# 07_FPGA_banks_1_2_3_4.net
KiCad netlist of a schematic drawn in Altium Designer
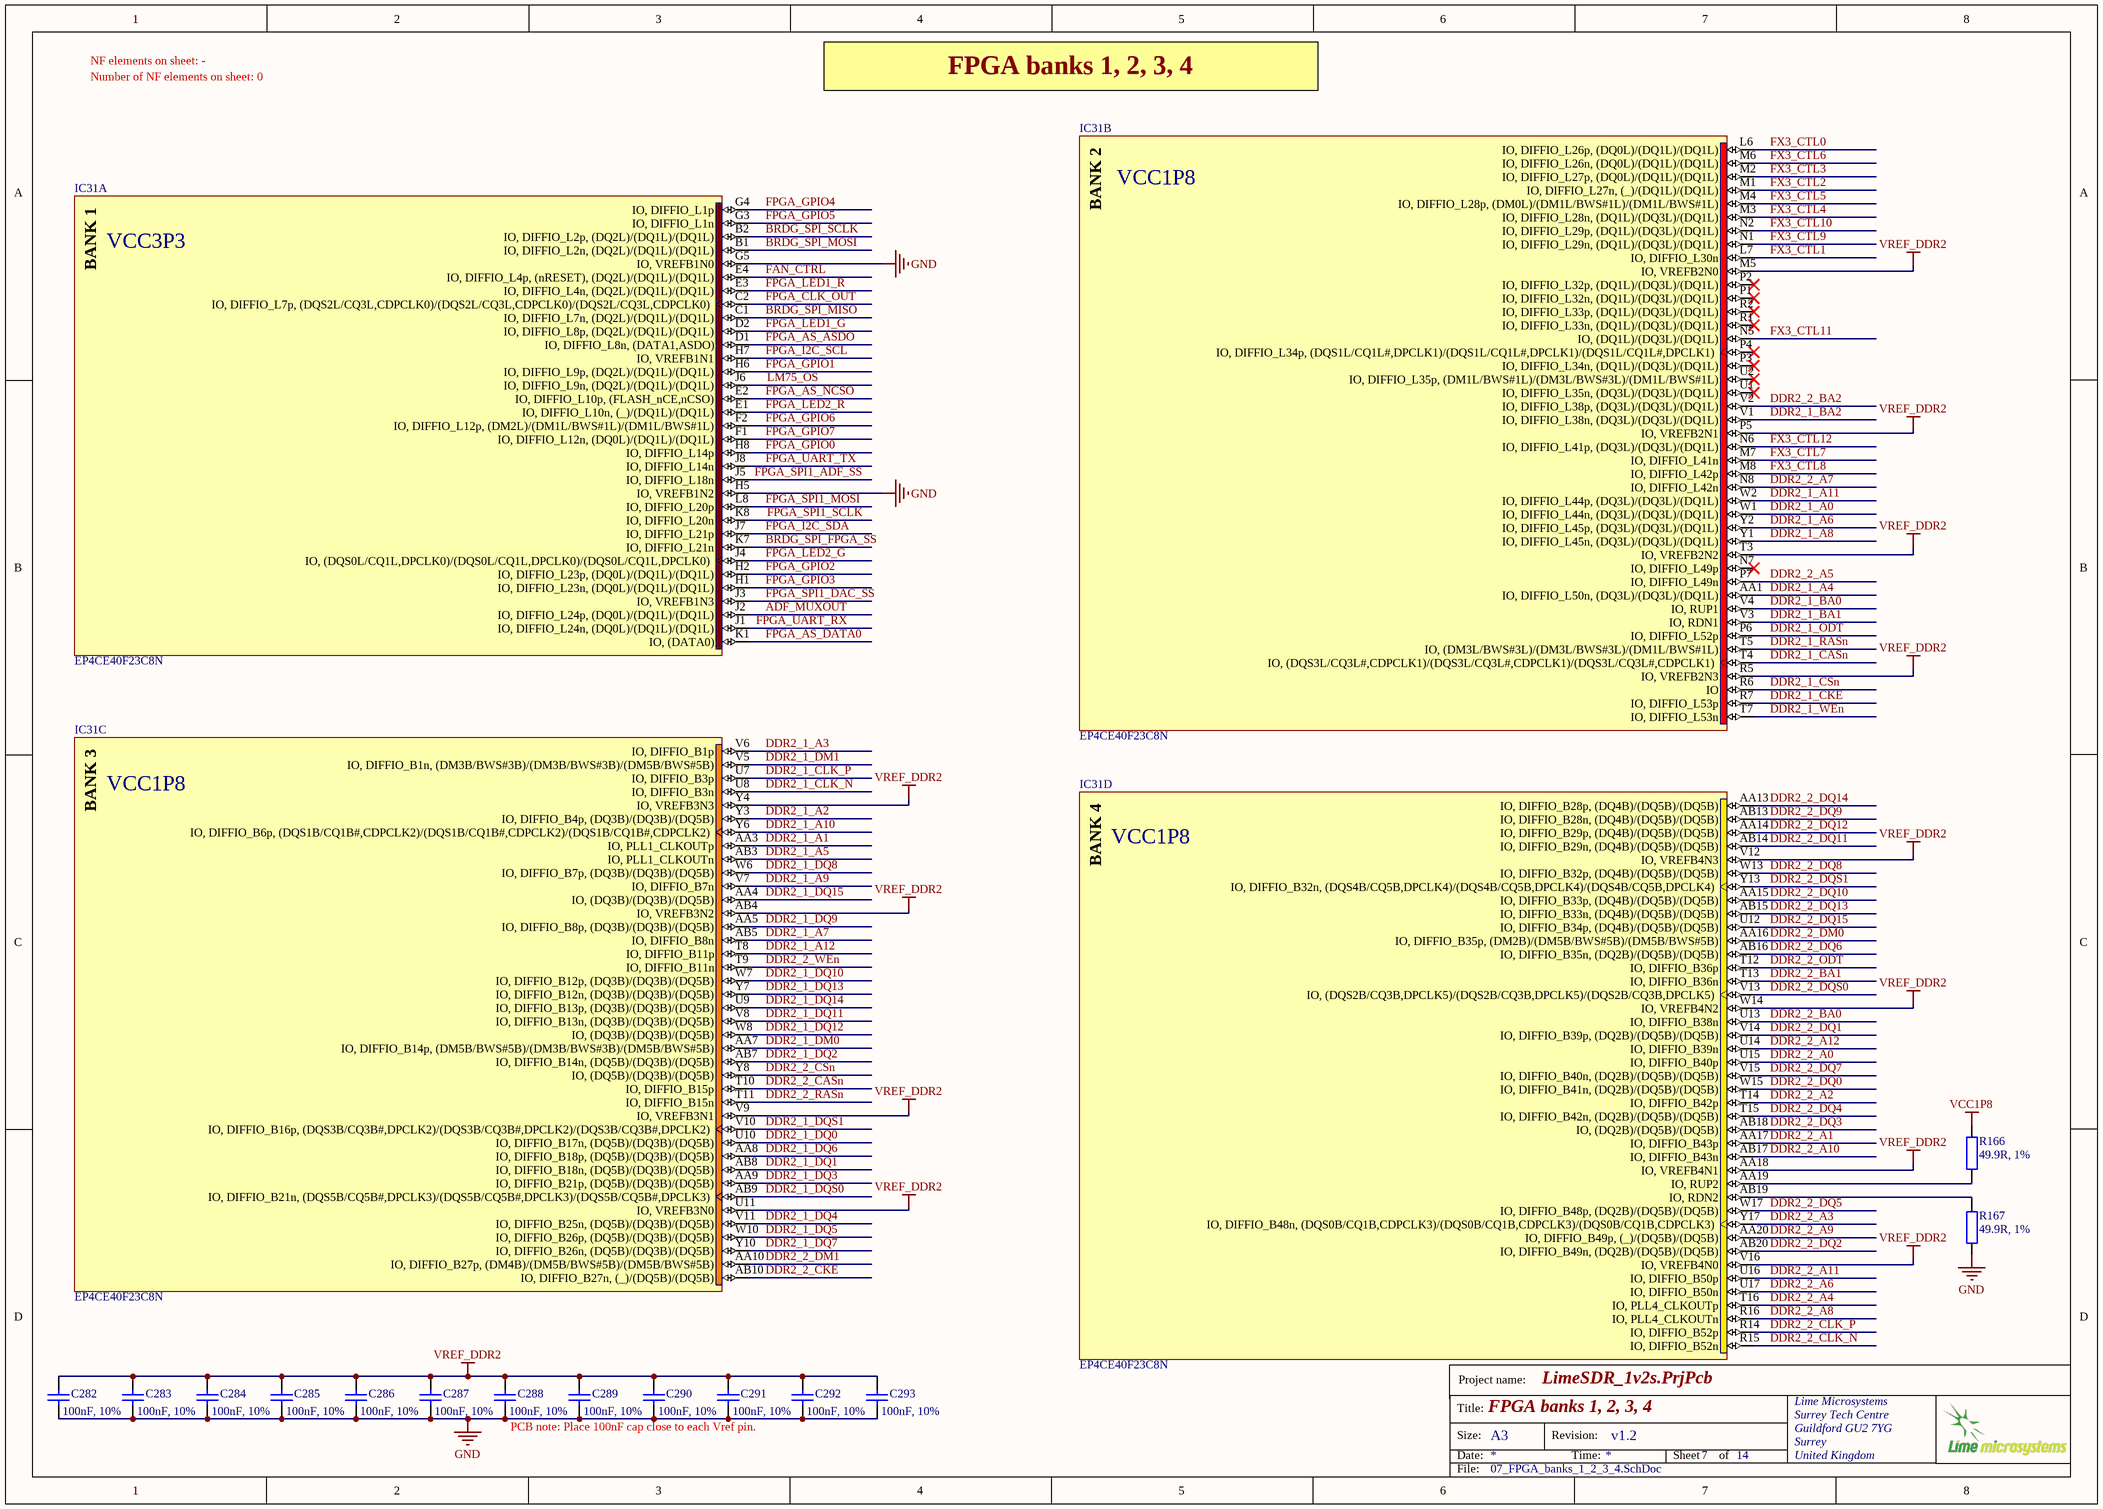
[diagram p0: 07_FPGA_banks_1_2_3_4.SchDoc]

(export (version "E")
  (design (tool "Eeschema 10.0.6"))
  (components
    (comp (ref "C282")
      (value "100nF, 10%")
      (footprint "CAP0402")
      (fields
        (field (name "TOLERANCE") "10 %")
        (field (name "MANUFACTURER") "Murata Electronics")
        (field (name "MANUFACTURER PART NUMBER") "GRM155R71C104KA88D")
      )
      (libsource (lib "LimeFPGAboard_schLib") (part "Cap_0603"))
    )
    (comp (ref "C283")
      (value "100nF, 10%")
      (footprint "CAP0402")
      (fields
        (field (name "TOLERANCE") "10 %")
        (field (name "MANUFACTURER") "Murata Electronics")
        (field (name "MANUFACTURER PART NUMBER") "GRM155R71C104KA88D")
      )
      (libsource (lib "LimeFPGAboard_schLib") (part "Cap_0603"))
    )
    (comp (ref "C284")
      (value "100nF, 10%")
      (footprint "CAP0402")
      (fields
        (field (name "TOLERANCE") "10 %")
        (field (name "MANUFACTURER") "Murata Electronics")
        (field (name "MANUFACTURER PART NUMBER") "GRM155R71C104KA88D")
      )
      (libsource (lib "LimeFPGAboard_schLib") (part "Cap_0603"))
    )
    (comp (ref "C285")
      (value "100nF, 10%")
      (footprint "CAP0402")
      (fields
        (field (name "TOLERANCE") "10 %")
        (field (name "MANUFACTURER") "Murata Electronics")
        (field (name "MANUFACTURER PART NUMBER") "GRM155R71C104KA88D")
      )
      (libsource (lib "LimeFPGAboard_schLib") (part "Cap_0603"))
    )
    (comp (ref "C286")
      (value "100nF, 10%")
      (footprint "CAP0402")
      (fields
        (field (name "TOLERANCE") "10 %")
        (field (name "MANUFACTURER") "Murata Electronics")
        (field (name "MANUFACTURER PART NUMBER") "GRM155R71C104KA88D")
      )
      (libsource (lib "LimeFPGAboard_schLib") (part "Cap_0603"))
    )
    (comp (ref "C287")
      (value "100nF, 10%")
      (footprint "CAP0402")
      (fields
        (field (name "TOLERANCE") "10 %")
        (field (name "MANUFACTURER") "Murata Electronics")
        (field (name "MANUFACTURER PART NUMBER") "GRM155R71C104KA88D")
      )
      (libsource (lib "LimeFPGAboard_schLib") (part "Cap_0603"))
    )
    (comp (ref "C288")
      (value "100nF, 10%")
      (footprint "CAP0402")
      (fields
        (field (name "TOLERANCE") "10 %")
        (field (name "MANUFACTURER") "Murata Electronics")
        (field (name "MANUFACTURER PART NUMBER") "GRM155R71C104KA88D")
      )
      (libsource (lib "LimeFPGAboard_schLib") (part "Cap_0603"))
    )
    (comp (ref "C289")
      (value "100nF, 10%")
      (footprint "CAP0402")
      (fields
        (field (name "TOLERANCE") "10 %")
        (field (name "MANUFACTURER") "Murata Electronics")
        (field (name "MANUFACTURER PART NUMBER") "GRM155R71C104KA88D")
      )
      (libsource (lib "LimeFPGAboard_schLib") (part "Cap_0603"))
    )
    (comp (ref "C290")
      (value "100nF, 10%")
      (footprint "CAP0402")
      (fields
        (field (name "TOLERANCE") "10 %")
        (field (name "MANUFACTURER") "Murata Electronics")
        (field (name "MANUFACTURER PART NUMBER") "GRM155R71C104KA88D")
      )
      (libsource (lib "LimeFPGAboard_schLib") (part "Cap_0603"))
    )
    (comp (ref "C291")
      (value "100nF, 10%")
      (footprint "CAP0402")
      (fields
        (field (name "TOLERANCE") "10 %")
        (field (name "MANUFACTURER") "Murata Electronics")
        (field (name "MANUFACTURER PART NUMBER") "GRM155R71C104KA88D")
      )
      (libsource (lib "LimeFPGAboard_schLib") (part "Cap_0603"))
    )
    (comp (ref "C292")
      (value "100nF, 10%")
      (footprint "CAP0402")
      (fields
        (field (name "TOLERANCE") "10 %")
        (field (name "MANUFACTURER") "Murata Electronics")
        (field (name "MANUFACTURER PART NUMBER") "GRM155R71C104KA88D")
      )
      (libsource (lib "LimeFPGAboard_schLib") (part "Cap_0603"))
    )
    (comp (ref "C293")
      (value "100nF, 10%")
      (footprint "CAP0402")
      (fields
        (field (name "TOLERANCE") "10 %")
        (field (name "MANUFACTURER") "Murata Electronics")
        (field (name "MANUFACTURER PART NUMBER") "GRM155R71C104KA88D")
      )
      (libsource (lib "LimeFPGAboard_schLib") (part "Cap_0603"))
    )
    (comp (ref "IC31")
      (value "EP4CE40F23C8N")
      (footprint "FBGA484_A-240")
      (description "IC FPGA 328 I/O 484FBGA")
      (fields (field (name "MANUFACTURER") "Altera"))
      (libsource (lib "LimeMicroAltiumLib_schLib") (part "EP4CE40F23C7N"))
    )
    (comp (ref "R166")
      (value "49.9R, 1%")
      (footprint "LimeMicroAltiumLib_pcbLib:RES0402")
      (fields
        (field (name "TOLERANCE") "±1%")
        (field (name "MANUFACTURER") "Samsung Electro-Mechanics America, Inc.")
        (field (name "MANUFACTURER PART NUMBER") "RC1005F49R9CS")
      )
      (libsource (lib "LimeMicroAltiumLib_schLib") (part "Res_0402"))
    )
    (comp (ref "R167")
      (value "49.9R, 1%")
      (footprint "LimeMicroAltiumLib_pcbLib:RES0402")
      (fields
        (field (name "TOLERANCE") "±1%")
        (field (name "MANUFACTURER") "Samsung Electro-Mechanics America, Inc.")
        (field (name "MANUFACTURER PART NUMBER") "RC1005F49R9CS")
      )
      (libsource (lib "LimeMicroAltiumLib_schLib") (part "Res_0402"))
    )
  )
  (nets
    (net (code "1") (name "/ADF_MUXOUT") (class "Default")
      (node (ref "IC31") (pin "J2") (pinfunction "IO,_DIFFIO_L24p,_(DQ0L)/(DQ1L)/(DQ1L)_J2") (pintype "bidirectional"))
    )
    (net (code "2") (name "/BRDG_SPI_FPGA_SS") (class "Default")
      (node (ref "IC31") (pin "K7") (pinfunction "IO,_DIFFIO_L21n_K7") (pintype "bidirectional"))
    )
    (net (code "3") (name "/BRDG_SPI_MISO") (class "Default")
      (node (ref "IC31") (pin "C1") (pinfunction "IO,_DIFFIO_L7n,_(DQ2L)/(DQ1L)/(DQ1L)_C1") (pintype "bidirectional"))
    )
    (net (code "4") (name "/BRDG_SPI_MOSI") (class "Default")
      (node (ref "IC31") (pin "B1") (pinfunction "IO,_DIFFIO_L2n,_(DQ2L)/(DQ1L)/(DQ1L)_B1") (pintype "bidirectional"))
    )
    (net (code "5") (name "/BRDG_SPI_SCLK") (class "Default")
      (node (ref "IC31") (pin "B2") (pinfunction "IO,_DIFFIO_L2p,_(DQ2L)/(DQ1L)/(DQ1L)_B2") (pintype "bidirectional"))
    )
    (net (code "6") (name "/DDR2_1_A0") (class "Default")
      (node (ref "IC31") (pin "W1") (pinfunction "IO,_DIFFIO_L44n,_(DQ3L)/(DQ3L)/(DQ1L)_W1") (pintype "bidirectional"))
    )
    (net (code "7") (name "/DDR2_1_A1") (class "Default")
      (node (ref "IC31") (pin "AA3") (pinfunction "IO,_PLL1_CLKOUTp_AA3") (pintype "bidirectional"))
    )
    (net (code "8") (name "/DDR2_1_A2") (class "Default")
      (node (ref "IC31") (pin "Y3") (pinfunction "IO,_DIFFIO_B4p,_(DQ3B)/(DQ3B)/(DQ5B)_Y3") (pintype "bidirectional"))
    )
    (net (code "9") (name "/DDR2_1_A3") (class "Default")
      (node (ref "IC31") (pin "V6") (pinfunction "IO,_DIFFIO_B1p_V6") (pintype "bidirectional"))
    )
    (net (code "10") (name "/DDR2_1_A4") (class "Default")
      (node (ref "IC31") (pin "AA1") (pinfunction "IO,_DIFFIO_L50n,_(DQ3L)/(DQ3L)/(DQ1L)_AA1") (pintype "bidirectional"))
    )
    (net (code "11") (name "/DDR2_1_A5") (class "Default")
      (node (ref "IC31") (pin "AB3") (pinfunction "IO,_PLL1_CLKOUTn_AB3") (pintype "bidirectional"))
    )
    (net (code "12") (name "/DDR2_1_A6") (class "Default")
      (node (ref "IC31") (pin "Y2") (pinfunction "IO,_DIFFIO_L45p,_(DQ3L)/(DQ3L)/(DQ1L)_Y2") (pintype "bidirectional"))
    )
    (net (code "13") (name "/DDR2_1_A7") (class "Default")
      (node (ref "IC31") (pin "AB5") (pinfunction "IO,_DIFFIO_B8n_AB5") (pintype "bidirectional"))
    )
    (net (code "14") (name "/DDR2_1_A8") (class "Default")
      (node (ref "IC31") (pin "Y1") (pinfunction "IO,_DIFFIO_L45n,_(DQ3L)/(DQ3L)/(DQ1L)_Y1") (pintype "bidirectional"))
    )
    (net (code "15") (name "/DDR2_1_A9") (class "Default")
      (node (ref "IC31") (pin "V7") (pinfunction "IO,_DIFFIO_B7n_V7") (pintype "bidirectional"))
    )
    (net (code "16") (name "/DDR2_1_A10") (class "Default")
      (node (ref "IC31") (pin "Y6") (pinfunction "IO,_DIFFIO_B6p,_(DQS1B/CQ1B#,CDPCLK2)/(DQS1B/CQ1B#,CDPCLK2)/(DQS1B/CQ1B#,CDPCLK2)_Y6") (pintype "bidirectional"))
    )
    (net (code "17") (name "/DDR2_1_A11") (class "Default")
      (node (ref "IC31") (pin "W2") (pinfunction "IO,_DIFFIO_L44p,_(DQ3L)/(DQ3L)/(DQ1L)_W2") (pintype "bidirectional"))
    )
    (net (code "18") (name "/DDR2_1_A12") (class "Default")
      (node (ref "IC31") (pin "T8") (pinfunction "IO,_DIFFIO_B11p_T8") (pintype "bidirectional"))
    )
    (net (code "19") (name "/DDR2_1_BA0") (class "Default")
      (node (ref "IC31") (pin "V4") (pinfunction "IO,_RUP1_V4") (pintype "bidirectional"))
    )
    (net (code "20") (name "/DDR2_1_BA1") (class "Default")
      (node (ref "IC31") (pin "V3") (pinfunction "IO,_RDN1_V3") (pintype "bidirectional"))
    )
    (net (code "21") (name "/DDR2_1_BA2") (class "Default")
      (node (ref "IC31") (pin "V1") (pinfunction "IO,_DIFFIO_L38n,_(DQ3L)/(DQ3L)/(DQ1L)_V1") (pintype "bidirectional"))
    )
    (net (code "22") (name "/DDR2_1_CASn") (class "Default")
      (node (ref "IC31") (pin "T4") (pinfunction "IO,_(DQS3L/CQ3L#,CDPCLK1)/(DQS3L/CQ3L#,CDPCLK1)/(DQS3L/CQ3L#,CDPCLK1)_T4") (pintype "bidirectional"))
    )
    (net (code "23") (name "/DDR2_1_CKE") (class "Default")
      (node (ref "IC31") (pin "R7") (pinfunction "IO,_DIFFIO_L53p_R7") (pintype "bidirectional"))
    )
    (net (code "24") (name "/DDR2_1_CLK_N") (class "Default")
      (node (ref "IC31") (pin "U8") (pinfunction "IO,_DIFFIO_B3n_U8") (pintype "bidirectional"))
    )
    (net (code "25") (name "/DDR2_1_CLK_P") (class "Default")
      (node (ref "IC31") (pin "U7") (pinfunction "IO,_DIFFIO_B3p_U7") (pintype "bidirectional"))
    )
    (net (code "26") (name "/DDR2_1_CSn") (class "Default")
      (node (ref "IC31") (pin "R6") (pinfunction "IO_R6") (pintype "bidirectional"))
    )
    (net (code "27") (name "/DDR2_1_DM0") (class "Default")
      (node (ref "IC31") (pin "AA7") (pinfunction "IO,_DIFFIO_B14p,_(DM5B/BWS#5B)/(DM3B/BWS#3B)/(DM5B/BWS#5B)_AA7") (pintype "bidirectional"))
    )
    (net (code "28") (name "/DDR2_1_DM1") (class "Default")
      (node (ref "IC31") (pin "V5") (pinfunction "IO,_DIFFIO_B1n,_(DM3B/BWS#3B)/(DM3B/BWS#3B)/(DM5B/BWS#5B)_V5") (pintype "bidirectional"))
    )
    (net (code "29") (name "/DDR2_1_DQ0") (class "Default")
      (node (ref "IC31") (pin "U10") (pinfunction "IO,_DIFFIO_B17n,_(DQ5B)/(DQ3B)/(DQ5B)_U10") (pintype "bidirectional"))
    )
    (net (code "30") (name "/DDR2_1_DQ1") (class "Default")
      (node (ref "IC31") (pin "AB8") (pinfunction "IO,_DIFFIO_B18n,_(DQ5B)/(DQ3B)/(DQ5B)_AB8") (pintype "bidirectional"))
    )
    (net (code "31") (name "/DDR2_1_DQ2") (class "Default")
      (node (ref "IC31") (pin "AB7") (pinfunction "IO,_DIFFIO_B14n,_(DQ5B)/(DQ3B)/(DQ5B)_AB7") (pintype "bidirectional"))
    )
    (net (code "32") (name "/DDR2_1_DQ3") (class "Default")
      (node (ref "IC31") (pin "AA9") (pinfunction "IO,_DIFFIO_B21p,_(DQ5B)/(DQ3B)/(DQ5B)_AA9") (pintype "bidirectional"))
    )
    (net (code "33") (name "/DDR2_1_DQ4") (class "Default")
      (node (ref "IC31") (pin "V11") (pinfunction "IO,_DIFFIO_B25n,_(DQ5B)/(DQ3B)/(DQ5B)_V11") (pintype "bidirectional"))
    )
    (net (code "34") (name "/DDR2_1_DQ5") (class "Default")
      (node (ref "IC31") (pin "W10") (pinfunction "IO,_DIFFIO_B26p,_(DQ5B)/(DQ3B)/(DQ5B)_W10") (pintype "bidirectional"))
    )
    (net (code "35") (name "/DDR2_1_DQ6") (class "Default")
      (node (ref "IC31") (pin "AA8") (pinfunction "IO,_DIFFIO_B18p,_(DQ5B)/(DQ3B)/(DQ5B)_AA8") (pintype "bidirectional"))
    )
    (net (code "36") (name "/DDR2_1_DQ7") (class "Default")
      (node (ref "IC31") (pin "Y10") (pinfunction "IO,_DIFFIO_B26n,_(DQ5B)/(DQ3B)/(DQ5B)_Y10") (pintype "bidirectional"))
    )
    (net (code "37") (name "/DDR2_1_DQ8") (class "Default")
      (node (ref "IC31") (pin "W6") (pinfunction "IO,_DIFFIO_B7p,_(DQ3B)/(DQ3B)/(DQ5B)_W6") (pintype "bidirectional"))
    )
    (net (code "38") (name "/DDR2_1_DQ9") (class "Default")
      (node (ref "IC31") (pin "AA5") (pinfunction "IO,_DIFFIO_B8p,_(DQ3B)/(DQ3B)/(DQ5B)_AA5") (pintype "bidirectional"))
    )
    (net (code "39") (name "/DDR2_1_DQ10") (class "Default")
      (node (ref "IC31") (pin "W7") (pinfunction "IO,_DIFFIO_B12p,_(DQ3B)/(DQ3B)/(DQ5B)_W7") (pintype "bidirectional"))
    )
    (net (code "40") (name "/DDR2_1_DQ11") (class "Default")
      (node (ref "IC31") (pin "V8") (pinfunction "IO,_DIFFIO_B13n,_(DQ3B)/(DQ3B)/(DQ5B)_V8") (pintype "bidirectional"))
    )
    (net (code "41") (name "/DDR2_1_DQ12") (class "Default")
      (node (ref "IC31") (pin "W8") (pinfunction "IO,_(DQ3B)/(DQ3B)/(DQ5B)_W8") (pintype "bidirectional"))
    )
    (net (code "42") (name "/DDR2_1_DQ13") (class "Default")
      (node (ref "IC31") (pin "Y7") (pinfunction "IO,_DIFFIO_B12n,_(DQ3B)/(DQ3B)/(DQ5B)_Y7") (pintype "bidirectional"))
    )
    (net (code "43") (name "/DDR2_1_DQ14") (class "Default")
      (node (ref "IC31") (pin "U9") (pinfunction "IO,_DIFFIO_B13p,_(DQ3B)/(DQ3B)/(DQ5B)_U9") (pintype "bidirectional"))
    )
    (net (code "44") (name "/DDR2_1_DQ15") (class "Default")
      (node (ref "IC31") (pin "AA4") (pinfunction "IO,_(DQ3B)/(DQ3B)/(DQ5B)_AA4") (pintype "bidirectional"))
    )
    (net (code "45") (name "/DDR2_1_DQS0") (class "Default")
      (node (ref "IC31") (pin "AB9") (pinfunction "IO,_DIFFIO_B21n,_(DQS5B/CQ5B#,DPCLK3)/(DQS5B/CQ5B#,DPCLK3)/(DQS5B/CQ5B#,DPCLK3)_AB9") (pintype "bidirectional"))
    )
    (net (code "46") (name "/DDR2_1_DQS1") (class "Default")
      (node (ref "IC31") (pin "V10") (pinfunction "IO,_DIFFIO_B16p,_(DQS3B/CQ3B#,DPCLK2)/(DQS3B/CQ3B#,DPCLK2)/(DQS3B/CQ3B#,DPCLK2)_V10") (pintype "bidirectional"))
    )
    (net (code "47") (name "/DDR2_1_ODT") (class "Default")
      (node (ref "IC31") (pin "P6") (pinfunction "IO,_DIFFIO_L52p_P6") (pintype "bidirectional"))
    )
    (net (code "48") (name "/DDR2_1_RASn") (class "Default")
      (node (ref "IC31") (pin "T5") (pinfunction "IO,_(DM3L/BWS#3L)/(DM3L/BWS#3L)/(DM1L/BWS#1L)_T5") (pintype "bidirectional"))
    )
    (net (code "49") (name "/DDR2_1_WEn") (class "Default")
      (node (ref "IC31") (pin "T7") (pinfunction "IO,_DIFFIO_L53n_T7") (pintype "bidirectional"))
    )
    (net (code "50") (name "/DDR2_2_A0") (class "Default")
      (node (ref "IC31") (pin "U15") (pinfunction "IO,_DIFFIO_B40p_U15") (pintype "bidirectional"))
    )
    (net (code "51") (name "/DDR2_2_A1") (class "Default")
      (node (ref "IC31") (pin "AA17") (pinfunction "IO,_DIFFIO_B43p_AA17") (pintype "bidirectional"))
    )
    (net (code "52") (name "/DDR2_2_A2") (class "Default")
      (node (ref "IC31") (pin "T14") (pinfunction "IO,_DIFFIO_B42p_T14") (pintype "bidirectional"))
    )
    (net (code "53") (name "/DDR2_2_A3") (class "Default")
      (node (ref "IC31") (pin "Y17") (pinfunction "IO,_DIFFIO_B48n,_(DQS0B/CQ1B,CDPCLK3)/(DQS0B/CQ1B,CDPCLK3)/(DQS0B/CQ1B,CDPCLK3)_Y17") (pintype "bidirectional"))
    )
    (net (code "54") (name "/DDR2_2_A4") (class "Default")
      (node (ref "IC31") (pin "T16") (pinfunction "IO,_PLL4_CLKOUTp_T16") (pintype "bidirectional"))
    )
    (net (code "55") (name "/DDR2_2_A5") (class "Default")
      (node (ref "IC31") (pin "P7") (pinfunction "IO,_DIFFIO_L49n_P7") (pintype "bidirectional"))
    )
    (net (code "56") (name "/DDR2_2_A6") (class "Default")
      (node (ref "IC31") (pin "U17") (pinfunction "IO,_DIFFIO_B50n_U17") (pintype "bidirectional"))
    )
    (net (code "57") (name "/DDR2_2_A7") (class "Default")
      (node (ref "IC31") (pin "N8") (pinfunction "IO,_DIFFIO_L42n_N8") (pintype "bidirectional"))
    )
    (net (code "58") (name "/DDR2_2_A8") (class "Default")
      (node (ref "IC31") (pin "R16") (pinfunction "IO,_PLL4_CLKOUTn_R16") (pintype "bidirectional"))
    )
    (net (code "59") (name "/DDR2_2_A9") (class "Default")
      (node (ref "IC31") (pin "AA20") (pinfunction "IO,_DIFFIO_B49p,_(_)/(DQ5B)/(DQ5B)_AA20") (pintype "bidirectional"))
    )
    (net (code "60") (name "/DDR2_2_A10") (class "Default")
      (node (ref "IC31") (pin "AB17") (pinfunction "IO,_DIFFIO_B43n_AB17") (pintype "bidirectional"))
    )
    (net (code "61") (name "/DDR2_2_A11") (class "Default")
      (node (ref "IC31") (pin "U16") (pinfunction "IO,_DIFFIO_B50p_U16") (pintype "bidirectional"))
    )
    (net (code "62") (name "/DDR2_2_A12") (class "Default")
      (node (ref "IC31") (pin "U14") (pinfunction "IO,_DIFFIO_B39n_U14") (pintype "bidirectional"))
    )
    (net (code "63") (name "/DDR2_2_BA0") (class "Default")
      (node (ref "IC31") (pin "U13") (pinfunction "IO,_DIFFIO_B38n_U13") (pintype "bidirectional"))
    )
    (net (code "64") (name "/DDR2_2_BA1") (class "Default")
      (node (ref "IC31") (pin "T13") (pinfunction "IO,_DIFFIO_B36n_T13") (pintype "bidirectional"))
    )
    (net (code "65") (name "/DDR2_2_BA2") (class "Default")
      (node (ref "IC31") (pin "V2") (pinfunction "IO,_DIFFIO_L38p,_(DQ3L)/(DQ3L)/(DQ1L)_V2") (pintype "bidirectional"))
    )
    (net (code "66") (name "/DDR2_2_CASn") (class "Default")
      (node (ref "IC31") (pin "T10") (pinfunction "IO,_DIFFIO_B15p_T10") (pintype "bidirectional"))
    )
    (net (code "67") (name "/DDR2_2_CKE") (class "Default")
      (node (ref "IC31") (pin "AB10") (pinfunction "IO,_DIFFIO_B27n,_(_)/(DQ5B)/(DQ5B)_AB10") (pintype "bidirectional"))
    )
    (net (code "68") (name "/DDR2_2_CLK_N") (class "Default")
      (node (ref "IC31") (pin "R15") (pinfunction "IO,_DIFFIO_B52n_R15") (pintype "bidirectional"))
    )
    (net (code "69") (name "/DDR2_2_CLK_P") (class "Default")
      (node (ref "IC31") (pin "R14") (pinfunction "IO,_DIFFIO_B52p_R14") (pintype "bidirectional"))
    )
    (net (code "70") (name "/DDR2_2_CSn") (class "Default")
      (node (ref "IC31") (pin "Y8") (pinfunction "IO,_(DQ5B)/(DQ3B)/(DQ5B)_Y8") (pintype "bidirectional"))
    )
    (net (code "71") (name "/DDR2_2_DM0") (class "Default")
      (node (ref "IC31") (pin "AA16") (pinfunction "IO,_DIFFIO_B35p,_(DM2B)/(DM5B/BWS#5B)/(DM5B/BWS#5B)_AA16") (pintype "bidirectional"))
    )
    (net (code "72") (name "/DDR2_2_DM1") (class "Default")
      (node (ref "IC31") (pin "AA10") (pinfunction "IO,_DIFFIO_B27p,_(DM4B)/(DM5B/BWS#5B)/(DM5B/BWS#5B)_AA10") (pintype "bidirectional"))
    )
    (net (code "73") (name "/DDR2_2_DQ0") (class "Default")
      (node (ref "IC31") (pin "W15") (pinfunction "IO,_DIFFIO_B41n,_(DQ2B)/(DQ5B)/(DQ5B)_W15") (pintype "bidirectional"))
    )
    (net (code "74") (name "/DDR2_2_DQ1") (class "Default")
      (node (ref "IC31") (pin "V14") (pinfunction "IO,_DIFFIO_B39p,_(DQ2B)/(DQ5B)/(DQ5B)_V14") (pintype "bidirectional"))
    )
    (net (code "75") (name "/DDR2_2_DQ2") (class "Default")
      (node (ref "IC31") (pin "AB20") (pinfunction "IO,_DIFFIO_B49n,_(DQ2B)/(DQ5B)/(DQ5B)_AB20") (pintype "bidirectional"))
    )
    (net (code "76") (name "/DDR2_2_DQ3") (class "Default")
      (node (ref "IC31") (pin "AB18") (pinfunction "IO,_(DQ2B)/(DQ5B)/(DQ5B)_AB18") (pintype "bidirectional"))
    )
    (net (code "77") (name "/DDR2_2_DQ4") (class "Default")
      (node (ref "IC31") (pin "T15") (pinfunction "IO,_DIFFIO_B42n,_(DQ2B)/(DQ5B)/(DQ5B)_T15") (pintype "bidirectional"))
    )
    (net (code "78") (name "/DDR2_2_DQ5") (class "Default")
      (node (ref "IC31") (pin "W17") (pinfunction "IO,_DIFFIO_B48p,_(DQ2B)/(DQ5B)/(DQ5B)_W17") (pintype "bidirectional"))
    )
    (net (code "79") (name "/DDR2_2_DQ6") (class "Default")
      (node (ref "IC31") (pin "AB16") (pinfunction "IO,_DIFFIO_B35n,_(DQ2B)/(DQ5B)/(DQ5B)_AB16") (pintype "bidirectional"))
    )
    (net (code "80") (name "/DDR2_2_DQ7") (class "Default")
      (node (ref "IC31") (pin "V15") (pinfunction "IO,_DIFFIO_B40n,_(DQ2B)/(DQ5B)/(DQ5B)_V15") (pintype "bidirectional"))
    )
    (net (code "81") (name "/DDR2_2_DQ8") (class "Default")
      (node (ref "IC31") (pin "W13") (pinfunction "IO,_DIFFIO_B32p,_(DQ4B)/(DQ5B)/(DQ5B)_W13") (pintype "bidirectional"))
    )
    (net (code "82") (name "/DDR2_2_DQ9") (class "Default")
      (node (ref "IC31") (pin "AB13") (pinfunction "IO,_DIFFIO_B28n,_(DQ4B)/(DQ5B)/(DQ5B)_AB13") (pintype "bidirectional"))
    )
    (net (code "83") (name "/DDR2_2_DQ10") (class "Default")
      (node (ref "IC31") (pin "AA15") (pinfunction "IO,_DIFFIO_B33p,_(DQ4B)/(DQ5B)/(DQ5B)_AA15") (pintype "bidirectional"))
    )
    (net (code "84") (name "/DDR2_2_DQ11") (class "Default")
      (node (ref "IC31") (pin "AB14") (pinfunction "IO,_DIFFIO_B29n,_(DQ4B)/(DQ5B)/(DQ5B)_AB14") (pintype "bidirectional"))
    )
    (net (code "85") (name "/DDR2_2_DQ12") (class "Default")
      (node (ref "IC31") (pin "AA14") (pinfunction "IO,_DIFFIO_B29p,_(DQ4B)/(DQ5B)/(DQ5B)_AA14") (pintype "bidirectional"))
    )
    (net (code "86") (name "/DDR2_2_DQ13") (class "Default")
      (node (ref "IC31") (pin "AB15") (pinfunction "IO,_DIFFIO_B33n,_(DQ4B)/(DQ5B)/(DQ5B)_AB15") (pintype "bidirectional"))
    )
    (net (code "87") (name "/DDR2_2_DQ14") (class "Default")
      (node (ref "IC31") (pin "AA13") (pinfunction "IO,_DIFFIO_B28p,_(DQ4B)/(DQ5B)/(DQ5B)_AA13") (pintype "bidirectional"))
    )
    (net (code "88") (name "/DDR2_2_DQ15") (class "Default")
      (node (ref "IC31") (pin "U12") (pinfunction "IO,_DIFFIO_B34p,_(DQ4B)/(DQ5B)/(DQ5B)_U12") (pintype "bidirectional"))
    )
    (net (code "89") (name "/DDR2_2_DQS0") (class "Default")
      (node (ref "IC31") (pin "V13") (pinfunction "IO,_(DQS2B/CQ3B,DPCLK5)/(DQS2B/CQ3B,DPCLK5)/(DQS2B/CQ3B,DPCLK5)_V13") (pintype "bidirectional"))
    )
    (net (code "90") (name "/DDR2_2_DQS1") (class "Default")
      (node (ref "IC31") (pin "Y13") (pinfunction "IO,_DIFFIO_B32n,_(DQS4B/CQ5B,DPCLK4)/(DQS4B/CQ5B,DPCLK4)/(DQS4B/CQ5B,DPCLK4)_Y13") (pintype "bidirectional"))
    )
    (net (code "91") (name "/DDR2_2_ODT") (class "Default")
      (node (ref "IC31") (pin "T12") (pinfunction "IO,_DIFFIO_B36p_T12") (pintype "bidirectional"))
    )
    (net (code "92") (name "/DDR2_2_RASn") (class "Default")
      (node (ref "IC31") (pin "T11") (pinfunction "IO,_DIFFIO_B15n_T11") (pintype "bidirectional"))
    )
    (net (code "93") (name "/DDR2_2_WEn") (class "Default")
      (node (ref "IC31") (pin "T9") (pinfunction "IO,_DIFFIO_B11n_T9") (pintype "bidirectional"))
    )
    (net (code "94") (name "/FAN_CTRL") (class "Default")
      (node (ref "IC31") (pin "E4") (pinfunction "IO,_DIFFIO_L4p,_(nRESET),_(DQ2L)/(DQ1L)/(DQ1L)_E4") (pintype "bidirectional"))
    )
    (net (code "95") (name "/FPGA_AS_ASDO") (class "Default")
      (node (ref "IC31") (pin "D1") (pinfunction "IO,_DIFFIO_L8n,_(DATA1,ASDO)_D1") (pintype "bidirectional"))
    )
    (net (code "96") (name "/FPGA_AS_DATA0") (class "Default")
      (node (ref "IC31") (pin "K1") (pinfunction "IO,_(DATA0)_K1") (pintype "bidirectional"))
    )
    (net (code "97") (name "/FPGA_AS_NCSO") (class "Default")
      (node (ref "IC31") (pin "E2") (pinfunction "IO,_DIFFIO_L10p,_(FLASH_nCE,nCSO)_E2") (pintype "bidirectional"))
    )
    (net (code "98") (name "/FPGA_CLK_OUT") (class "Default")
      (node (ref "IC31") (pin "C2") (pinfunction "IO,_DIFFIO_L7p,_(DQS2L/CQ3L,CDPCLK0)/(DQS2L/CQ3L,CDPCLK0)/(DQS2L/CQ3L,CDPCLK0)_C2") (pintype "bidirectional"))
    )
    (net (code "99") (name "/FPGA_GPIO0") (class "Default")
      (node (ref "IC31") (pin "H8") (pinfunction "IO,_DIFFIO_L14p_H8") (pintype "bidirectional"))
    )
    (net (code "100") (name "/FPGA_GPIO1") (class "Default")
      (node (ref "IC31") (pin "H6") (pinfunction "IO,_DIFFIO_L9p,_(DQ2L)/(DQ1L)/(DQ1L)_H6") (pintype "bidirectional"))
    )
    (net (code "101") (name "/FPGA_GPIO2") (class "Default")
      (node (ref "IC31") (pin "H2") (pinfunction "IO,_DIFFIO_L23p,_(DQ0L)/(DQ1L)/(DQ1L)_H2") (pintype "bidirectional"))
    )
    (net (code "102") (name "/FPGA_GPIO3") (class "Default")
      (node (ref "IC31") (pin "H1") (pinfunction "IO,_DIFFIO_L23n,_(DQ0L)/(DQ1L)/(DQ1L)_H1") (pintype "bidirectional"))
    )
    (net (code "103") (name "/FPGA_GPIO4") (class "Default")
      (node (ref "IC31") (pin "G4") (pinfunction "IO,_DIFFIO_L1p_G4") (pintype "bidirectional"))
    )
    (net (code "104") (name "/FPGA_GPIO5") (class "Default")
      (node (ref "IC31") (pin "G3") (pinfunction "IO,_DIFFIO_L1n_G3") (pintype "bidirectional"))
    )
    (net (code "105") (name "/FPGA_GPIO6") (class "Default")
      (node (ref "IC31") (pin "F2") (pinfunction "IO,_DIFFIO_L12p,_(DM2L)/(DM1L/BWS#1L)/(DM1L/BWS#1L)_F2") (pintype "bidirectional"))
    )
    (net (code "106") (name "/FPGA_GPIO7") (class "Default")
      (node (ref "IC31") (pin "F1") (pinfunction "IO,_DIFFIO_L12n,_(DQ0L)/(DQ1L)/(DQ1L)_F1") (pintype "bidirectional"))
    )
    (net (code "107") (name "/FPGA_I2C_SCL") (class "Default")
      (node (ref "IC31") (pin "H7") (pinfunction "IO,_VREFB1N1_H7") (pintype "bidirectional"))
    )
    (net (code "108") (name "/FPGA_I2C_SDA") (class "Default")
      (node (ref "IC31") (pin "J7") (pinfunction "IO,_DIFFIO_L21p_J7") (pintype "bidirectional"))
    )
    (net (code "109") (name "/FPGA_LED1_G") (class "Default")
      (node (ref "IC31") (pin "D2") (pinfunction "IO,_DIFFIO_L8p,_(DQ2L)/(DQ1L)/(DQ1L)_D2") (pintype "bidirectional"))
    )
    (net (code "110") (name "/FPGA_LED1_R") (class "Default")
      (node (ref "IC31") (pin "E3") (pinfunction "IO,_DIFFIO_L4n,_(DQ2L)/(DQ1L)/(DQ1L)_E3") (pintype "bidirectional"))
    )
    (net (code "111") (name "/FPGA_LED2_G") (class "Default")
      (node (ref "IC31") (pin "J4") (pinfunction "IO,_(DQS0L/CQ1L,DPCLK0)/(DQS0L/CQ1L,DPCLK0)/(DQS0L/CQ1L,DPCLK0)_J4") (pintype "bidirectional"))
    )
    (net (code "112") (name "/FPGA_LED2_R") (class "Default")
      (node (ref "IC31") (pin "E1") (pinfunction "IO,_DIFFIO_L10n,_(_)/(DQ1L)/(DQ1L)_E1") (pintype "bidirectional"))
    )
    (net (code "113") (name "/FPGA_SPI1_ADF_SS") (class "Default")
      (node (ref "IC31") (pin "J5") (pinfunction "IO,_DIFFIO_L18n_J5") (pintype "bidirectional"))
    )
    (net (code "114") (name "/FPGA_SPI1_DAC_SS") (class "Default")
      (node (ref "IC31") (pin "J3") (pinfunction "IO,_VREFB1N3_J3") (pintype "bidirectional"))
    )
    (net (code "115") (name "/FPGA_SPI1_MOSI") (class "Default")
      (node (ref "IC31") (pin "L8") (pinfunction "IO,_DIFFIO_L20p_L8") (pintype "bidirectional"))
    )
    (net (code "116") (name "/FPGA_SPI1_SCLK") (class "Default")
      (node (ref "IC31") (pin "K8") (pinfunction "IO,_DIFFIO_L20n_K8") (pintype "bidirectional"))
    )
    (net (code "117") (name "/FPGA_UART_RX") (class "Default")
      (node (ref "IC31") (pin "J1") (pinfunction "IO,_DIFFIO_L24n,_(DQ0L)/(DQ1L)/(DQ1L)_J1") (pintype "bidirectional"))
    )
    (net (code "118") (name "/FPGA_UART_TX") (class "Default")
      (node (ref "IC31") (pin "J8") (pinfunction "IO,_DIFFIO_L14n_J8") (pintype "bidirectional"))
    )
    (net (code "119") (name "/FX3_CTL0") (class "Default")
      (node (ref "IC31") (pin "L6") (pinfunction "IO,_DIFFIO_L26p,_(DQ0L)/(DQ1L)/(DQ1L)_L6") (pintype "bidirectional"))
    )
    (net (code "120") (name "/FX3_CTL1") (class "Default")
      (node (ref "IC31") (pin "L7") (pinfunction "IO,_DIFFIO_L30n_L7") (pintype "bidirectional"))
    )
    (net (code "121") (name "/FX3_CTL2") (class "Default")
      (node (ref "IC31") (pin "M1") (pinfunction "IO,_DIFFIO_L27n,_(_)/(DQ1L)/(DQ1L)_M1") (pintype "bidirectional"))
    )
    (net (code "122") (name "/FX3_CTL3") (class "Default")
      (node (ref "IC31") (pin "M2") (pinfunction "IO,_DIFFIO_L27p,_(DQ0L)/(DQ1L)/(DQ1L)_M2") (pintype "bidirectional"))
    )
    (net (code "123") (name "/FX3_CTL4") (class "Default")
      (node (ref "IC31") (pin "M3") (pinfunction "IO,_DIFFIO_L28n,_(DQ1L)/(DQ3L)/(DQ1L)_M3") (pintype "bidirectional"))
    )
    (net (code "124") (name "/FX3_CTL5") (class "Default")
      (node (ref "IC31") (pin "M4") (pinfunction "IO,_DIFFIO_L28p,_(DM0L)/(DM1L/BWS#1L)/(DM1L/BWS#1L)_M4") (pintype "bidirectional"))
    )
    (net (code "125") (name "/FX3_CTL6") (class "Default")
      (node (ref "IC31") (pin "M6") (pinfunction "IO,_DIFFIO_L26n,_(DQ0L)/(DQ1L)/(DQ1L)_M6") (pintype "bidirectional"))
    )
    (net (code "126") (name "/FX3_CTL7") (class "Default")
      (node (ref "IC31") (pin "M7") (pinfunction "IO,_DIFFIO_L41n_M7") (pintype "bidirectional"))
    )
    (net (code "127") (name "/FX3_CTL8") (class "Default")
      (node (ref "IC31") (pin "M8") (pinfunction "IO,_DIFFIO_L42p_M8") (pintype "bidirectional"))
    )
    (net (code "128") (name "/FX3_CTL9") (class "Default")
      (node (ref "IC31") (pin "N1") (pinfunction "IO,_DIFFIO_L29n,_(DQ1L)/(DQ3L)/(DQ1L)_N1") (pintype "bidirectional"))
    )
    (net (code "129") (name "/FX3_CTL10") (class "Default")
      (node (ref "IC31") (pin "N2") (pinfunction "IO,_DIFFIO_L29p,_(DQ1L)/(DQ3L)/(DQ1L)_N2") (pintype "bidirectional"))
    )
    (net (code "130") (name "/FX3_CTL11") (class "Default")
      (node (ref "IC31") (pin "N5") (pinfunction "IO,_(DQ1L)/(DQ3L)/(DQ1L)_N5") (pintype "bidirectional"))
    )
    (net (code "131") (name "/FX3_CTL12") (class "Default")
      (node (ref "IC31") (pin "N6") (pinfunction "IO,_DIFFIO_L41p,_(DQ3L)/(DQ3L)/(DQ1L)_N6") (pintype "bidirectional"))
    )
    (net (code "132") (name "/LM75_OS") (class "Default")
      (node (ref "IC31") (pin "J6") (pinfunction "IO,_DIFFIO_L9n,_(DQ2L)/(DQ1L)/(DQ1L)_J6") (pintype "bidirectional"))
    )
    (net (code "133") (name "GND") (class "Default")
      (node (ref "C282") (pin "2") (pinfunction "2_2") (pintype "passive"))
      (node (ref "C283") (pin "2") (pinfunction "2_2") (pintype "passive"))
      (node (ref "C284") (pin "2") (pinfunction "2_2") (pintype "passive"))
      (node (ref "C285") (pin "2") (pinfunction "2_2") (pintype "passive"))
      (node (ref "C286") (pin "2") (pinfunction "2_2") (pintype "passive"))
      (node (ref "C287") (pin "2") (pinfunction "2_2") (pintype "passive"))
      (node (ref "C288") (pin "2") (pinfunction "2_2") (pintype "passive"))
      (node (ref "C289") (pin "2") (pinfunction "2_2") (pintype "passive"))
      (node (ref "C290") (pin "2") (pinfunction "2_2") (pintype "passive"))
      (node (ref "C291") (pin "2") (pinfunction "2_2") (pintype "passive"))
      (node (ref "C292") (pin "2") (pinfunction "2_2") (pintype "passive"))
      (node (ref "C293") (pin "2") (pinfunction "2_2") (pintype "passive"))
      (node (ref "IC31") (pin "G5") (pinfunction "IO,_VREFB1N0_G5") (pintype "bidirectional"))
      (node (ref "IC31") (pin "H5") (pinfunction "IO,_VREFB1N2_H5") (pintype "bidirectional"))
      (node (ref "R167") (pin "1") (pinfunction "1_1") (pintype "passive"))
    )
    (net (code "134") (name "Net-(IC31D-IO,_RDN2)") (class "Default")
      (node (ref "IC31") (pin "AB19") (pinfunction "IO,_RDN2_AB19") (pintype "bidirectional"))
      (node (ref "R167") (pin "2") (pinfunction "2_2") (pintype "passive"))
    )
    (net (code "135") (name "Net-(IC31D-IO,_RUP2)") (class "Default")
      (node (ref "IC31") (pin "AA19") (pinfunction "IO,_RUP2_AA19") (pintype "bidirectional"))
      (node (ref "R166") (pin "1") (pinfunction "1_1") (pintype "passive"))
    )
    (net (code "136") (name "VCC1P8") (class "Default")
      (node (ref "R166") (pin "2") (pinfunction "2_2") (pintype "passive"))
    )
    (net (code "137") (name "VREF_DDR2") (class "Default")
      (node (ref "C282") (pin "1") (pinfunction "1_1") (pintype "passive"))
      (node (ref "C283") (pin "1") (pinfunction "1_1") (pintype "passive"))
      (node (ref "C284") (pin "1") (pinfunction "1_1") (pintype "passive"))
      (node (ref "C285") (pin "1") (pinfunction "1_1") (pintype "passive"))
      (node (ref "C286") (pin "1") (pinfunction "1_1") (pintype "passive"))
      (node (ref "C287") (pin "1") (pinfunction "1_1") (pintype "passive"))
      (node (ref "C288") (pin "1") (pinfunction "1_1") (pintype "passive"))
      (node (ref "C289") (pin "1") (pinfunction "1_1") (pintype "passive"))
      (node (ref "C290") (pin "1") (pinfunction "1_1") (pintype "passive"))
      (node (ref "C291") (pin "1") (pinfunction "1_1") (pintype "passive"))
      (node (ref "C292") (pin "1") (pinfunction "1_1") (pintype "passive"))
      (node (ref "C293") (pin "1") (pinfunction "1_1") (pintype "passive"))
      (node (ref "IC31") (pin "AA18") (pinfunction "IO,_VREFB4N1_AA18") (pintype "bidirectional"))
      (node (ref "IC31") (pin "AB4") (pinfunction "IO,_VREFB3N2_AB4") (pintype "bidirectional"))
      (node (ref "IC31") (pin "M5") (pinfunction "IO,_VREFB2N0_M5") (pintype "bidirectional"))
      (node (ref "IC31") (pin "P5") (pinfunction "IO,_VREFB2N1_P5") (pintype "bidirectional"))
      (node (ref "IC31") (pin "R5") (pinfunction "IO,_VREFB2N3_R5") (pintype "bidirectional"))
      (node (ref "IC31") (pin "T3") (pinfunction "IO,_VREFB2N2_T3") (pintype "bidirectional"))
      (node (ref "IC31") (pin "U11") (pinfunction "IO,_VREFB3N0_U11") (pintype "bidirectional"))
      (node (ref "IC31") (pin "V12") (pinfunction "IO,_VREFB4N3_V12") (pintype "bidirectional"))
      (node (ref "IC31") (pin "V16") (pinfunction "IO,_VREFB4N0_V16") (pintype "bidirectional"))
      (node (ref "IC31") (pin "V9") (pinfunction "IO,_VREFB3N1_V9") (pintype "bidirectional"))
      (node (ref "IC31") (pin "W14") (pinfunction "IO,_VREFB4N2_W14") (pintype "bidirectional"))
      (node (ref "IC31") (pin "Y4") (pinfunction "IO,_VREFB3N3_Y4") (pintype "bidirectional"))
    )
    (net (code "138") (name "unconnected-(IC31B-IO,_DIFFIO_L32n,_(DQ1L){slash}(DQ3L){slash}(DQ1L)-PadP1)") (class "Default")
      (node (ref "IC31") (pin "P1") (pinfunction "IO,_DIFFIO_L32n,_(DQ1L)/(DQ3L)/(DQ1L)_P1") (pintype "bidirectional+no_connect"))
    )
    (net (code "139") (name "unconnected-(IC31B-IO,_DIFFIO_L32p,_(DQ1L){slash}(DQ3L){slash}(DQ1L)-PadP2)") (class "Default")
      (node (ref "IC31") (pin "P2") (pinfunction "IO,_DIFFIO_L32p,_(DQ1L)/(DQ3L)/(DQ1L)_P2") (pintype "bidirectional+no_connect"))
    )
    (net (code "140") (name "unconnected-(IC31B-IO,_DIFFIO_L33n,_(DQ1L){slash}(DQ3L){slash}(DQ1L)-PadR1)") (class "Default")
      (node (ref "IC31") (pin "R1") (pinfunction "IO,_DIFFIO_L33n,_(DQ1L)/(DQ3L)/(DQ1L)_R1") (pintype "bidirectional+no_connect"))
    )
    (net (code "141") (name "unconnected-(IC31B-IO,_DIFFIO_L33p,_(DQ1L){slash}(DQ3L){slash}(DQ1L)-PadR2)") (class "Default")
      (node (ref "IC31") (pin "R2") (pinfunction "IO,_DIFFIO_L33p,_(DQ1L)/(DQ3L)/(DQ1L)_R2") (pintype "bidirectional+no_connect"))
    )
    (net (code "142") (name "unconnected-(IC31B-IO,_DIFFIO_L34n,_(DQ1L){slash}(DQ3L){slash}(DQ1L)-PadP3)") (class "Default")
      (node (ref "IC31") (pin "P3") (pinfunction "IO,_DIFFIO_L34n,_(DQ1L)/(DQ3L)/(DQ1L)_P3") (pintype "bidirectional+no_connect"))
    )
    (net (code "143") (name "unconnected-(IC31B-IO,_DIFFIO_L34p,_(DQS1L{slash}CQ1L#,DPCLK1){slash}(DQS1L{slash}CQ1L#,DPCLK1){slash}(DQS1L{slash}CQ1L#,DPCLK1)-PadP4)") (class "Default")
      (node (ref "IC31") (pin "P4") (pinfunction "IO,_DIFFIO_L34p,_(DQS1L/CQ1L#,DPCLK1)/(DQS1L/CQ1L#,DPCLK1)/(DQS1L/CQ1L#,DPCLK1)_P4") (pintype "bidirectional+no_connect"))
    )
    (net (code "144") (name "unconnected-(IC31B-IO,_DIFFIO_L35n,_(DQ3L){slash}(DQ3L){slash}(DQ1L)-PadU1)") (class "Default")
      (node (ref "IC31") (pin "U1") (pinfunction "IO,_DIFFIO_L35n,_(DQ3L)/(DQ3L)/(DQ1L)_U1") (pintype "bidirectional+no_connect"))
    )
    (net (code "145") (name "unconnected-(IC31B-IO,_DIFFIO_L35p,_(DM1L{slash}BWS#1L){slash}(DM3L{slash}BWS#3L){slash}(DM1L{slash}BWS#1L)-PadU2)") (class "Default")
      (node (ref "IC31") (pin "U2") (pinfunction "IO,_DIFFIO_L35p,_(DM1L/BWS#1L)/(DM3L/BWS#3L)/(DM1L/BWS#1L)_U2") (pintype "bidirectional+no_connect"))
    )
    (net (code "146") (name "unconnected-(IC31B-IO,_DIFFIO_L49p-PadN7)") (class "Default")
      (node (ref "IC31") (pin "N7") (pinfunction "IO,_DIFFIO_L49p_N7") (pintype "bidirectional+no_connect"))
    )
  )
)
